# ProPrj_Fallout_card_2026-06-22.net
KiCad netlist of a schematic drawn in EasyEDA Pro
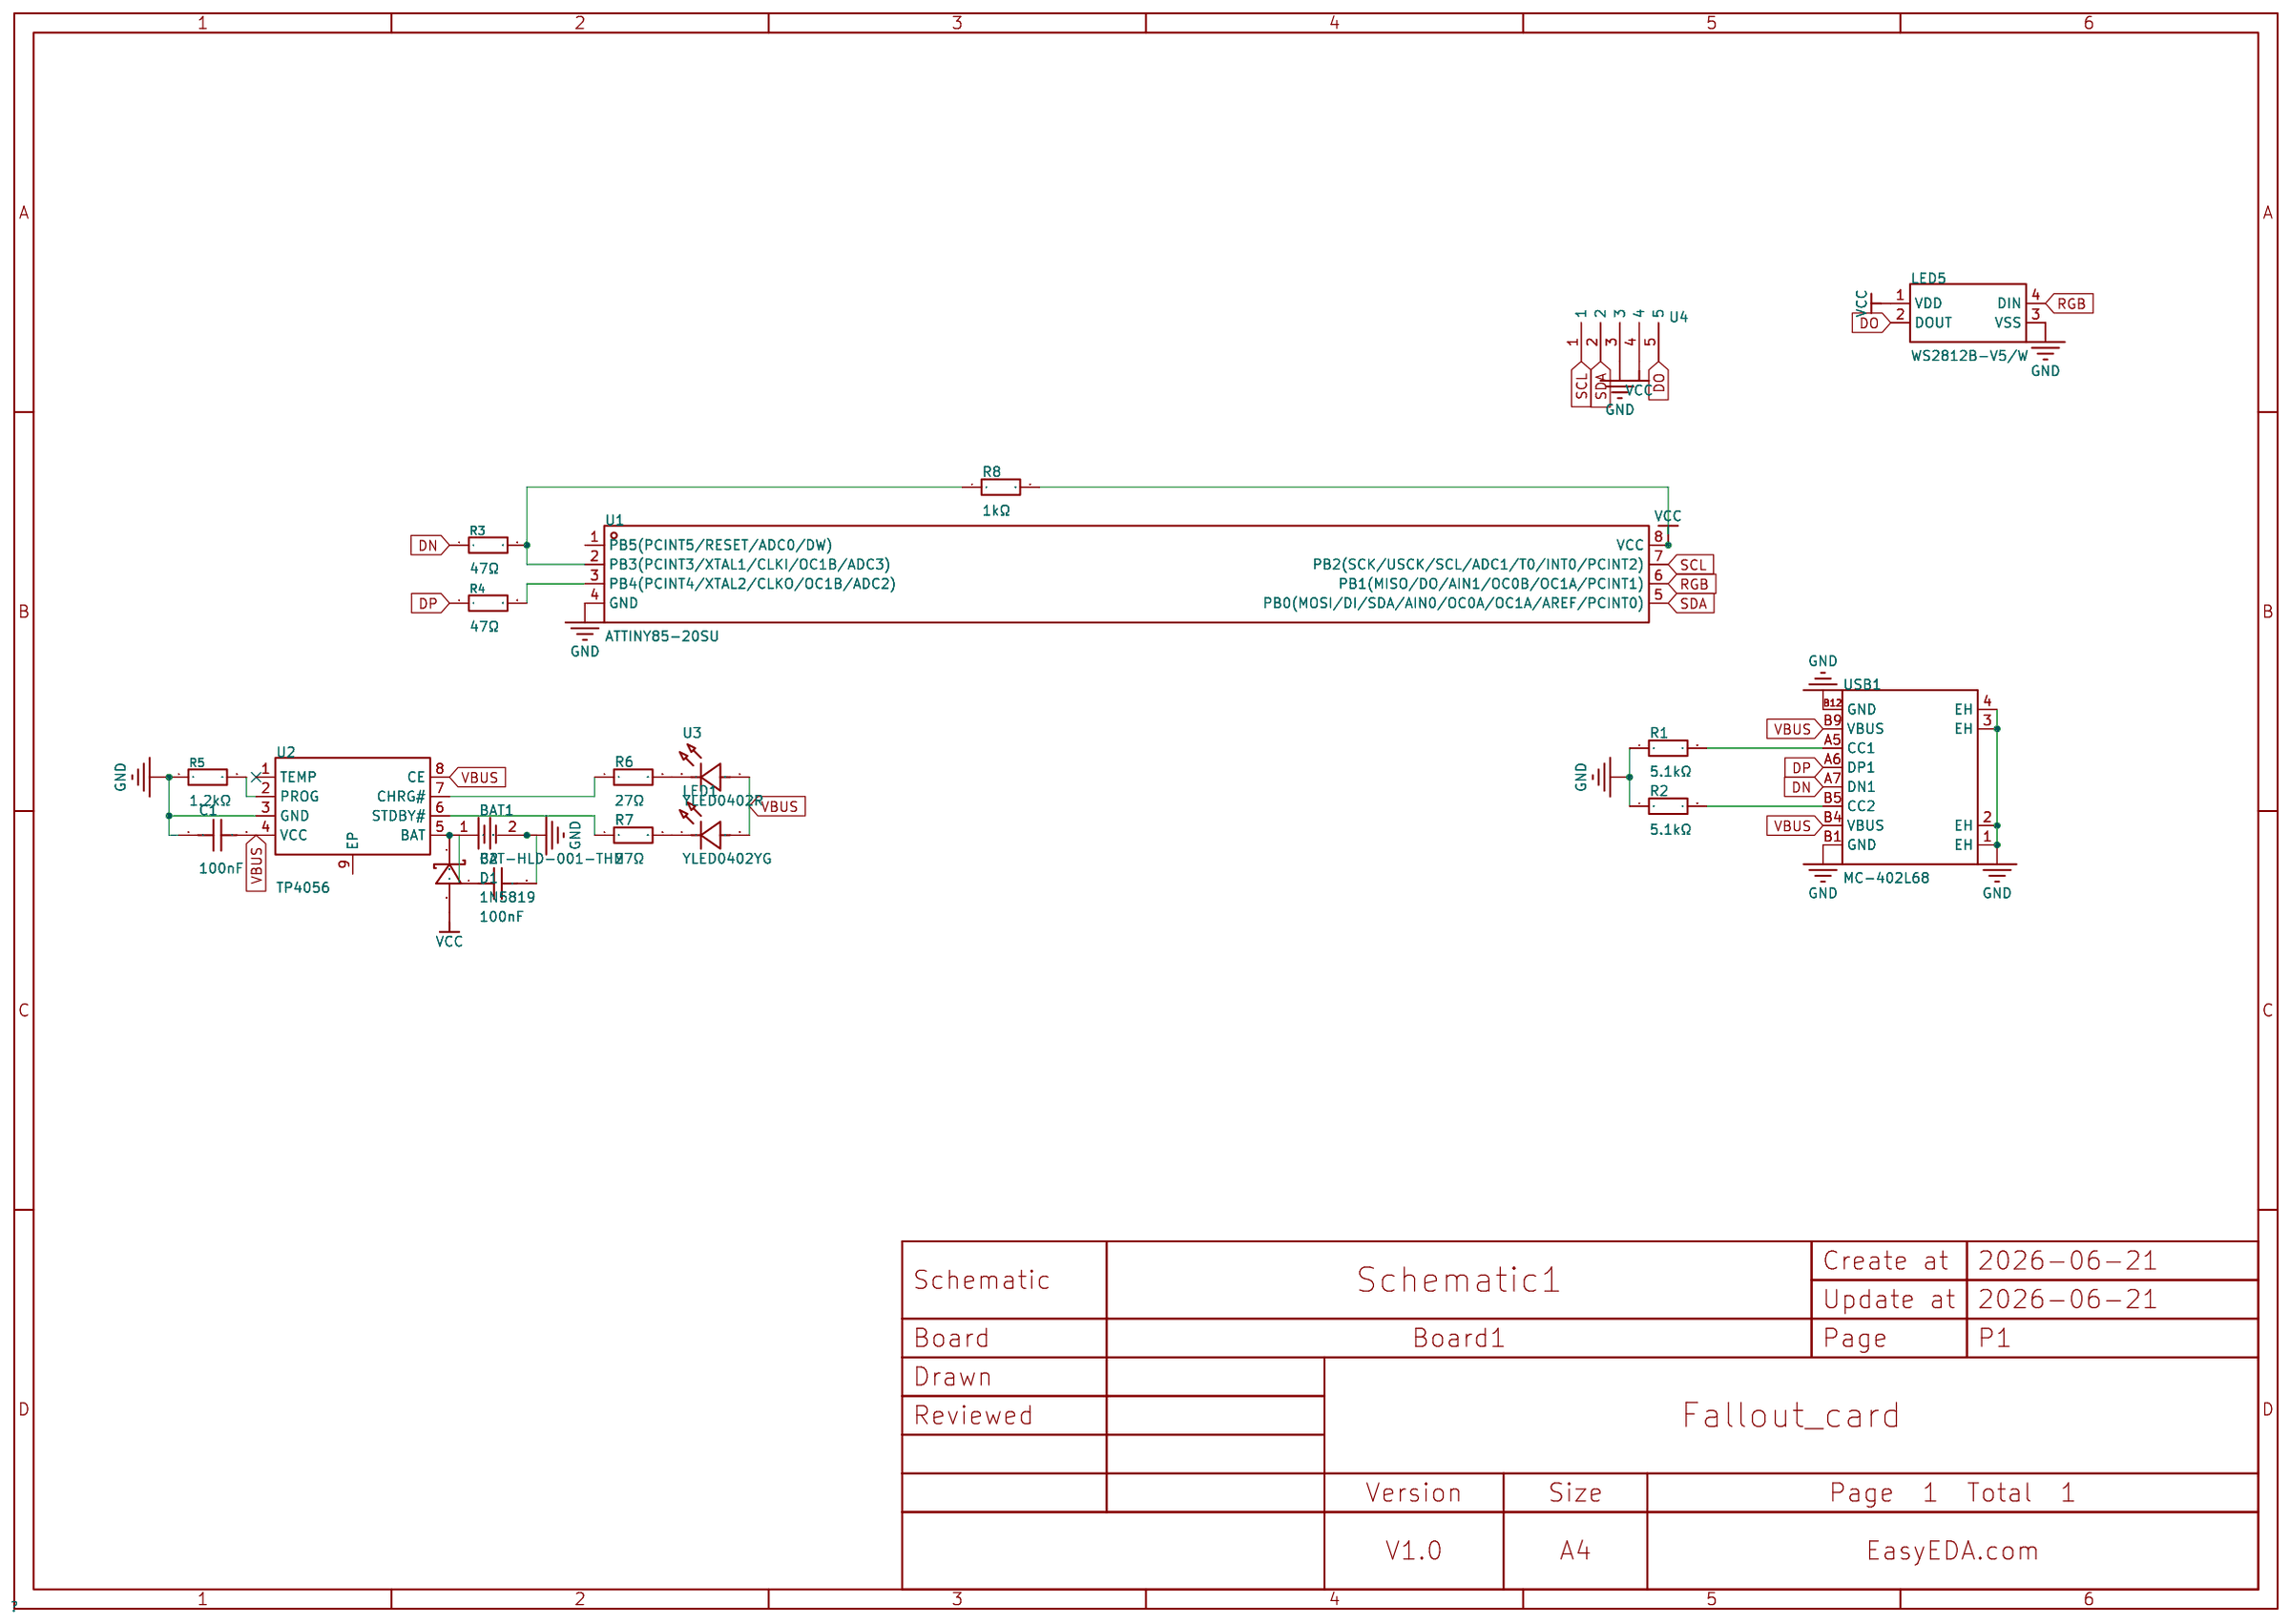
[diagram p0: schematic sheet]

(export (version "E")
  (design (tool "Eeschema 10.0.6"))
  (components
    (comp (ref "BAT1")
      (value "BAT-HLD-001-THM")
      (footprint "easyedapro:BAT-TH_BAT-HLD-001-THM_1")
      (fields (field (name "Manufacturer") "TE Connectivity(泰科电子)"))
      (libsource (lib "easyedapro") (part "BAT-HLD-001-THM"))
    )
    (comp (ref "C1")
      (value "100nF")
      (footprint "easyedapro:C0402")
      (fields
        (field (name "Manufacturer Part") "GRM155B31H104KE14D")
        (field (name "Manufacturer") "muRata(村田)")
      )
      (libsource (lib "easyedapro") (part "GRM155B31H104KE14D"))
    )
    (comp (ref "C2")
      (value "100nF")
      (footprint "easyedapro:C0402")
      (fields
        (field (name "Manufacturer Part") "GRM155B31H104KE14D")
        (field (name "Manufacturer") "muRata(村田)")
      )
      (libsource (lib "easyedapro") (part "GRM155B31H104KE14D"))
    )
    (comp (ref "D1")
      (value "1N5819")
      (footprint "easyedapro:SMA_L4.4-W2.6-LS5.0-RD")
      (fields (field (name "Manufacturer") "KEXIN(科信)"))
      (libsource (lib "easyedapro") (part "1N5819_C437199"))
    )
    (comp (ref "LED1")
      (value "YLED0402YG")
      (footprint "easyedapro:LED0402-RD")
      (fields (field (name "Manufacturer") "YONGYUTAI(永裕泰)"))
      (libsource (lib "easyedapro") (part "YLED0402YG"))
    )
    (comp (ref "LED5")
      (value "WS2812B-V5/W")
      (footprint "easyedapro:LED-SMD_4P-L5.0-W5.0-TL-1")
      (fields (field (name "Manufacturer") "worldsemi"))
      (libsource (lib "easyedapro") (part "WS2812B-V5/W"))
    )
    (comp (ref "R1")
      (value "5.1kΩ")
      (footprint "easyedapro:R0402")
      (fields (field (name "Manufacturer Part") "RMC04025.1K5%N") (field (name "Manufacturer") "Tyohm(幸亚电阻)"))
      (libsource (lib "easyedapro") (part "RMC04025.1K5%N"))
    )
    (comp (ref "R2")
      (value "5.1kΩ")
      (footprint "easyedapro:R0402")
      (fields (field (name "Manufacturer Part") "RMC04025.1K5%N") (field (name "Manufacturer") "Tyohm(幸亚电阻)"))
      (libsource (lib "easyedapro") (part "RMC04025.1K5%N"))
    )
    (comp (ref "R3")
      (value "47Ω")
      (footprint "easyedapro:R0402")
      (fields (field (name "Manufacturer Part") "RTT0247R0FTH") (field (name "Manufacturer") "RALEC(旺诠)"))
      (libsource (lib "easyedapro") (part "RTT0247R0FTH"))
    )
    (comp (ref "R4")
      (value "47Ω")
      (footprint "easyedapro:R0402")
      (fields (field (name "Manufacturer Part") "RTT0247R0FTH") (field (name "Manufacturer") "RALEC(旺诠)"))
      (libsource (lib "easyedapro") (part "RTT0247R0FTH"))
    )
    (comp (ref "R5")
      (value "1.2kΩ")
      (footprint "easyedapro:R0402")
      (fields (field (name "Manufacturer Part") "RMC04021.2K5%N") (field (name "Manufacturer") "Tyohm(幸亚电阻)"))
      (libsource (lib "easyedapro") (part "RMC04021.2K5%N"))
    )
    (comp (ref "R6")
      (value "27Ω")
      (footprint "easyedapro:R0402")
      (fields (field (name "Manufacturer Part") "RMS04JT270") (field (name "Manufacturer") "大毅科技"))
      (libsource (lib "easyedapro") (part "RMS04JT270"))
    )
    (comp (ref "R7")
      (value "27Ω")
      (footprint "easyedapro:R0402")
      (fields (field (name "Manufacturer Part") "RMS04JT270") (field (name "Manufacturer") "大毅科技"))
      (libsource (lib "easyedapro") (part "RMS04JT270"))
    )
    (comp (ref "R8")
      (value "1kΩ")
      (footprint "easyedapro:R0402")
      (fields (field (name "Manufacturer Part") "RT0402FRE071KL") (field (name "Manufacturer") "YAGEO(国巨)"))
      (libsource (lib "easyedapro") (part "RT0402FRE071KL"))
    )
    (comp (ref "U1")
      (value "ATTINY85-20SU")
      (footprint "easyedapro:SOIC-8_L5.3-W5.3-P1.27-LS8.0-BL")
      (fields (field (name "Manufacturer") "MICROCHIP(美国微芯)"))
      (libsource (lib "easyedapro") (part "ATTINY85-20SU_C31540447"))
    )
    (comp (ref "U2")
      (value "TP4056")
      (footprint "easyedapro:ESOP-8_L4.9-W3.9-P1.27-LS6.0-BL-EP-1")
      (fields (field (name "Manufacturer") "HICHON(海川)"))
      (libsource (lib "easyedapro") (part "TP4056_C49045948"))
    )
    (comp (ref "U3")
      (value "YLED0402R")
      (footprint "easyedapro:LED0402-R-RD")
      (fields (field (name "Manufacturer") "YONGYUTAI(永裕泰)"))
      (libsource (lib "easyedapro") (part "YLED0402R"))
    )
    (comp (ref "U4")
      (value "~")
      (footprint "easyedapro:PAD'S")
      (libsource (lib "easyedapro") (part "pad's for tiny mcu"))
    )
    (comp (ref "USB1")
      (value "MC-402L68")
      (footprint "easyedapro:USB-C-SMD_MC-402L68")
      (fields (field (name "Manufacturer") "HANBO(汉博)"))
      (libsource (lib "easyedapro") (part "MC-402L68"))
    )
  )
  (nets
    (net (code "1") (name "DN") (class "Default")
      (node (ref "R3") (pin "1") (pinfunction "1_1") (pintype "input"))
      (node (ref "USB1") (pin "A7") (pinfunction "DN1_A7") (pintype "unspecified"))
    )
    (net (code "2") (name "DO") (class "Default")
      (node (ref "LED5") (pin "2") (pinfunction "DOUT_2") (pintype "unspecified"))
      (node (ref "U4") (pin "5") (pinfunction "5_5") (pintype "unspecified"))
    )
    (net (code "3") (name "DP") (class "Default")
      (node (ref "R4") (pin "1") (pinfunction "1_1") (pintype "input"))
      (node (ref "USB1") (pin "A6") (pinfunction "DP1_A6") (pintype "unspecified"))
    )
    (net (code "4") (name "GND") (class "Default")
      (node (ref "BAT1") (pin "2") (pinfunction "2_2") (pintype "input"))
      (node (ref "C1") (pin "1") (pinfunction "1_1") (pintype "unspecified"))
      (node (ref "C2") (pin "2") (pinfunction "2_2") (pintype "unspecified"))
      (node (ref "LED5") (pin "3") (pinfunction "VSS_3") (pintype "unspecified"))
      (node (ref "R1") (pin "1") (pinfunction "1_1") (pintype "unspecified"))
      (node (ref "R2") (pin "1") (pinfunction "1_1") (pintype "unspecified"))
      (node (ref "R5") (pin "1") (pinfunction "1_1") (pintype "input"))
      (node (ref "U1") (pin "4") (pinfunction "GND_4") (pintype "unspecified"))
      (node (ref "U2") (pin "3") (pinfunction "GND_3") (pintype "unspecified"))
      (node (ref "U4") (pin "3") (pinfunction "3_3") (pintype "unspecified"))
      (node (ref "USB1") (pin "1") (pinfunction "EH_1") (pintype "unspecified"))
      (node (ref "USB1") (pin "2") (pinfunction "EH_2") (pintype "unspecified"))
      (node (ref "USB1") (pin "3") (pinfunction "EH_3") (pintype "unspecified"))
      (node (ref "USB1") (pin "4") (pinfunction "EH_4") (pintype "unspecified"))
      (node (ref "USB1") (pin "B1") (pinfunction "GND_B1") (pintype "unspecified"))
      (node (ref "USB1") (pin "B12") (pinfunction "GND_B12") (pintype "unspecified"))
    )
    (net (code "5") (name "Net-(D1-C)") (class "Default")
      (node (ref "BAT1") (pin "1") (pinfunction "1_1") (pintype "input"))
      (node (ref "C2") (pin "1") (pinfunction "1_1") (pintype "unspecified"))
      (node (ref "D1") (pin "1") (pinfunction "C_1") (pintype "unspecified"))
      (node (ref "U2") (pin "5") (pinfunction "BAT_5") (pintype "unspecified"))
    )
    (net (code "6") (name "Net-(LED1-K)") (class "Default")
      (node (ref "LED1") (pin "1") (pinfunction "K_1") (pintype "unspecified"))
      (node (ref "R7") (pin "2") (pinfunction "2_2") (pintype "input"))
    )
    (net (code "7") (name "Net-(U1-PB3(PCINT3{slash}XTAL1{slash}CLKI{slash}OC1B{slash}ADC3))") (class "Default")
      (node (ref "R3") (pin "2") (pinfunction "2_2") (pintype "input"))
      (node (ref "R8") (pin "1") (pinfunction "1_1") (pintype "unspecified"))
      (node (ref "U1") (pin "2") (pinfunction "PB3(PCINT3/XTAL1/CLKI/OC1B/ADC3)_2") (pintype "unspecified"))
    )
    (net (code "8") (name "Net-(U1-PB4(PCINT4{slash}XTAL2{slash}CLKO{slash}OC1B{slash}ADC2))") (class "Default")
      (node (ref "R4") (pin "2") (pinfunction "2_2") (pintype "input"))
      (node (ref "U1") (pin "3") (pinfunction "PB4(PCINT4/XTAL2/CLKO/OC1B/ADC2)_3") (pintype "unspecified"))
    )
    (net (code "9") (name "Net-(U2-CHRG#)") (class "Default")
      (node (ref "R6") (pin "1") (pinfunction "1_1") (pintype "input"))
      (node (ref "U2") (pin "7") (pinfunction "CHRG#_7") (pintype "unspecified"))
    )
    (net (code "10") (name "Net-(U2-PROG)") (class "Default")
      (node (ref "R5") (pin "2") (pinfunction "2_2") (pintype "input"))
      (node (ref "U2") (pin "2") (pinfunction "PROG_2") (pintype "unspecified"))
    )
    (net (code "11") (name "Net-(U2-STDBY#)") (class "Default")
      (node (ref "R7") (pin "1") (pinfunction "1_1") (pintype "input"))
      (node (ref "U2") (pin "6") (pinfunction "STDBY#_6") (pintype "unspecified"))
    )
    (net (code "12") (name "Net-(U3-K)") (class "Default")
      (node (ref "R6") (pin "2") (pinfunction "2_2") (pintype "input"))
      (node (ref "U3") (pin "2") (pinfunction "K_2") (pintype "unspecified"))
    )
    (net (code "13") (name "Net-(USB1-CC1)") (class "Default")
      (node (ref "R1") (pin "2") (pinfunction "2_2") (pintype "unspecified"))
      (node (ref "USB1") (pin "A5") (pinfunction "CC1_A5") (pintype "unspecified"))
    )
    (net (code "14") (name "Net-(USB1-CC2)") (class "Default")
      (node (ref "R2") (pin "2") (pinfunction "2_2") (pintype "unspecified"))
      (node (ref "USB1") (pin "B5") (pinfunction "CC2_B5") (pintype "unspecified"))
    )
    (net (code "15") (name "RGB") (class "Default")
      (node (ref "LED5") (pin "4") (pinfunction "DIN_4") (pintype "unspecified"))
      (node (ref "U1") (pin "6") (pinfunction "PB1(MISO/DO/AIN1/OC0B/OC1A/PCINT1)_6") (pintype "unspecified"))
    )
    (net (code "16") (name "SCL") (class "Default")
      (node (ref "U1") (pin "7") (pinfunction "PB2(SCK/USCK/SCL/ADC1/T0/INT0/PCINT2)_7") (pintype "unspecified"))
      (node (ref "U4") (pin "1") (pinfunction "1_1") (pintype "unspecified"))
    )
    (net (code "17") (name "SDA") (class "Default")
      (node (ref "U1") (pin "5") (pinfunction "PB0(MOSI/DI/SDA/AIN0/OC0A/OC1A/AREF/PCINT0)_5") (pintype "unspecified"))
      (node (ref "U4") (pin "2") (pinfunction "2_2") (pintype "unspecified"))
    )
    (net (code "18") (name "VBUS") (class "Default")
      (node (ref "C1") (pin "2") (pinfunction "2_2") (pintype "unspecified"))
      (node (ref "LED1") (pin "2") (pinfunction "A_2") (pintype "unspecified"))
      (node (ref "U2") (pin "4") (pinfunction "VCC_4") (pintype "unspecified"))
      (node (ref "U2") (pin "8") (pinfunction "CE_8") (pintype "unspecified"))
      (node (ref "U3") (pin "1") (pinfunction "A_1") (pintype "unspecified"))
      (node (ref "USB1") (pin "B4") (pinfunction "VBUS_B4") (pintype "unspecified"))
      (node (ref "USB1") (pin "B9") (pinfunction "VBUS_B9") (pintype "unspecified"))
    )
    (net (code "19") (name "VCC") (class "Default")
      (node (ref "D1") (pin "2") (pinfunction "A_2") (pintype "unspecified"))
      (node (ref "LED5") (pin "1") (pinfunction "VDD_1") (pintype "unspecified"))
      (node (ref "R8") (pin "2") (pinfunction "2_2") (pintype "unspecified"))
      (node (ref "U1") (pin "8") (pinfunction "VCC_8") (pintype "unspecified"))
      (node (ref "U4") (pin "4") (pinfunction "4_4") (pintype "unspecified"))
    )
    (net (code "20") (name "unconnected-(U1-PB5(PCINT5{slash}RESET{slash}ADC0{slash}DW)-Pad1)") (class "Default")
      (node (ref "U1") (pin "1") (pinfunction "PB5(PCINT5/RESET/ADC0/DW)_1") (pintype "unspecified"))
    )
    (net (code "21") (name "unconnected-(U2-EP-Pad9)") (class "Default")
      (node (ref "U2") (pin "9") (pinfunction "EP_9") (pintype "unspecified"))
    )
    (net (code "22") (name "unconnected-(U2-TEMP-Pad1)") (class "Default")
      (node (ref "U2") (pin "1") (pinfunction "TEMP_1") (pintype "unspecified+no_connect"))
    )
  )
)
